# Relay.net
KiCad netlist of a schematic drawn in Altium Designer
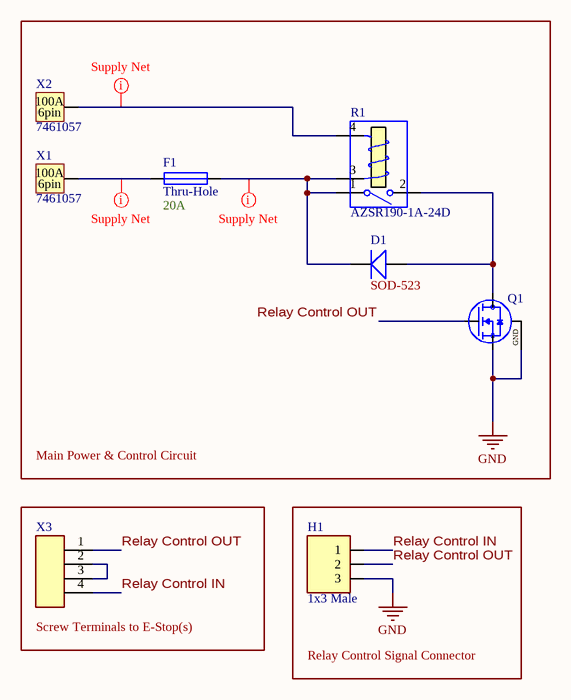
[diagram p0: Relay.SchDoc]

(export (version "E")
  (design (tool "Eeschema 10.0.6"))
  (components
    (comp (ref "D1")
      (value "Rectifier")
      (footprint "[Diode] SMD SOD-523")
      (description "Generic")
      (fields (field (name "SIZE PACKAGE") "SOD-523"))
      (libsource (lib "RADM Components") (part "[Diode] SMD Rectifier"))
    )
    (comp (ref "F1")
      (value "Thru-Hole")
      (footprint "[Fuse] Thru-Hole Blade")
      (fields (field (name "CAPACITY") "20A"))
      (libsource (lib "RADM Components") (part "[Fuse] Thru-Hole Blade"))
    )
    (comp (ref "H1")
      (value "1x3 Male")
      (footprint "[Header] Shrouded 1x3 Male")
      (description "070543-0037\r\nMates with 005057-9403")
      (libsource (lib "RADM Connectors") (part "[Header] Shrouded 1x3 Male"))
    )
    (comp (ref "Q1")
      (value "[FET] NMOS IRF610PBF")
      (footprint "[FET] NMOS IRF610PBF")
      (description "N-Channel 200 V 3.3A (Tc) 36W (Tc) Through Hole TO-220AB")
      (libsource (lib "RADM Components") (part "[FET] NMOS IRF610PBF"))
    )
    (comp (ref "R1")
      (value "AZSR190-1A-24D")
      (footprint "[Relay] AZSR190-1A-24D")
      (libsource (lib "RADM Components") (part "[Relay] AZSR190-1A-24D"))
    )
    (comp (ref "X1")
      (value "7461057")
      (footprint "[Port] Shank Connector (100A)")
      (description "7461057, internal thread")
      (libsource (lib "RADM Connectors") (part "[Port] Shank Connector (100A)"))
    )
    (comp (ref "X2")
      (value "7461057")
      (footprint "[Port] Shank Connector (100A)")
      (description "7461057, internal thread")
      (libsource (lib "RADM Connectors") (part "[Port] Shank Connector (100A)"))
    )
    (comp (ref "X3")
      (value "4pin Screw Terminal")
      (footprint "[Screw Terminal] 4pin 5mm")
      (libsource (lib "RADM Connectors") (part "[Screw Terminal] 4pin"))
    )
  )
  (nets
    (net (code "1") (name "/Relay Control IN") (class "Default")
      (node (ref "H1") (pin "1") (pinfunction "1_1") (pintype "passive"))
      (node (ref "X3") (pin "4") (pintype "power_in"))
    )
    (net (code "2") (name "/Relay Control OUT") (class "Default")
      (node (ref "H1") (pin "2") (pinfunction "2_2") (pintype "passive"))
      (node (ref "Q1") (pin "G") (pinfunction "Gate_G") (pintype "passive"))
      (node (ref "X3") (pin "1") (pintype "power_in"))
    )
    (net (code "3") (name "GND") (class "Default")
      (node (ref "H1") (pin "3") (pinfunction "3_3") (pintype "passive"))
      (node (ref "Q1") (pin "S") (pinfunction "Source_S") (pintype "passive"))
      (node (ref "Q1") (pin "X") (pinfunction "GND_X") (pintype "passive"))
    )
    (net (code "4") (name "Net-(D1-Anode)") (class "Default")
      (node (ref "D1") (pin "2") (pinfunction "Anode_2") (pintype "power_in"))
      (node (ref "Q1") (pin "D") (pinfunction "Drain_D") (pintype "passive"))
      (node (ref "R1") (pin "2") (pinfunction "2_2") (pintype "passive"))
    )
    (net (code "5") (name "Net-(D1-Cathode)") (class "Default")
      (node (ref "D1") (pin "1") (pinfunction "Cathode_1") (pintype "power_in"))
      (node (ref "F1") (pin "2") (pinfunction "2_2") (pintype "passive"))
      (node (ref "R1") (pin "1") (pinfunction "1_1") (pintype "passive"))
      (node (ref "R1") (pin "3") (pinfunction "T1_3") (pintype "passive"))
    )
    (net (code "6") (name "Net-(R1-T2)") (class "Default")
      (node (ref "R1") (pin "4") (pinfunction "T2_4") (pintype "passive"))
      (node (ref "X2") (pin "1") (pinfunction "4_1") (pintype "power_in"))
    )
    (net (code "7") (name "Net-(X1-4)") (class "Default")
      (node (ref "F1") (pin "1") (pinfunction "1_1") (pintype "passive"))
      (node (ref "X1") (pin "1") (pinfunction "4_1") (pintype "power_in"))
    )
    (net (code "8") (name "Net-(X3-Pad2)") (class "Default")
      (node (ref "X3") (pin "2") (pintype "power_in"))
      (node (ref "X3") (pin "3") (pintype "power_in"))
    )
  )
)
